# overpoweredRedLight.net
KiCad netlist of a schematic drawn in EAGLE
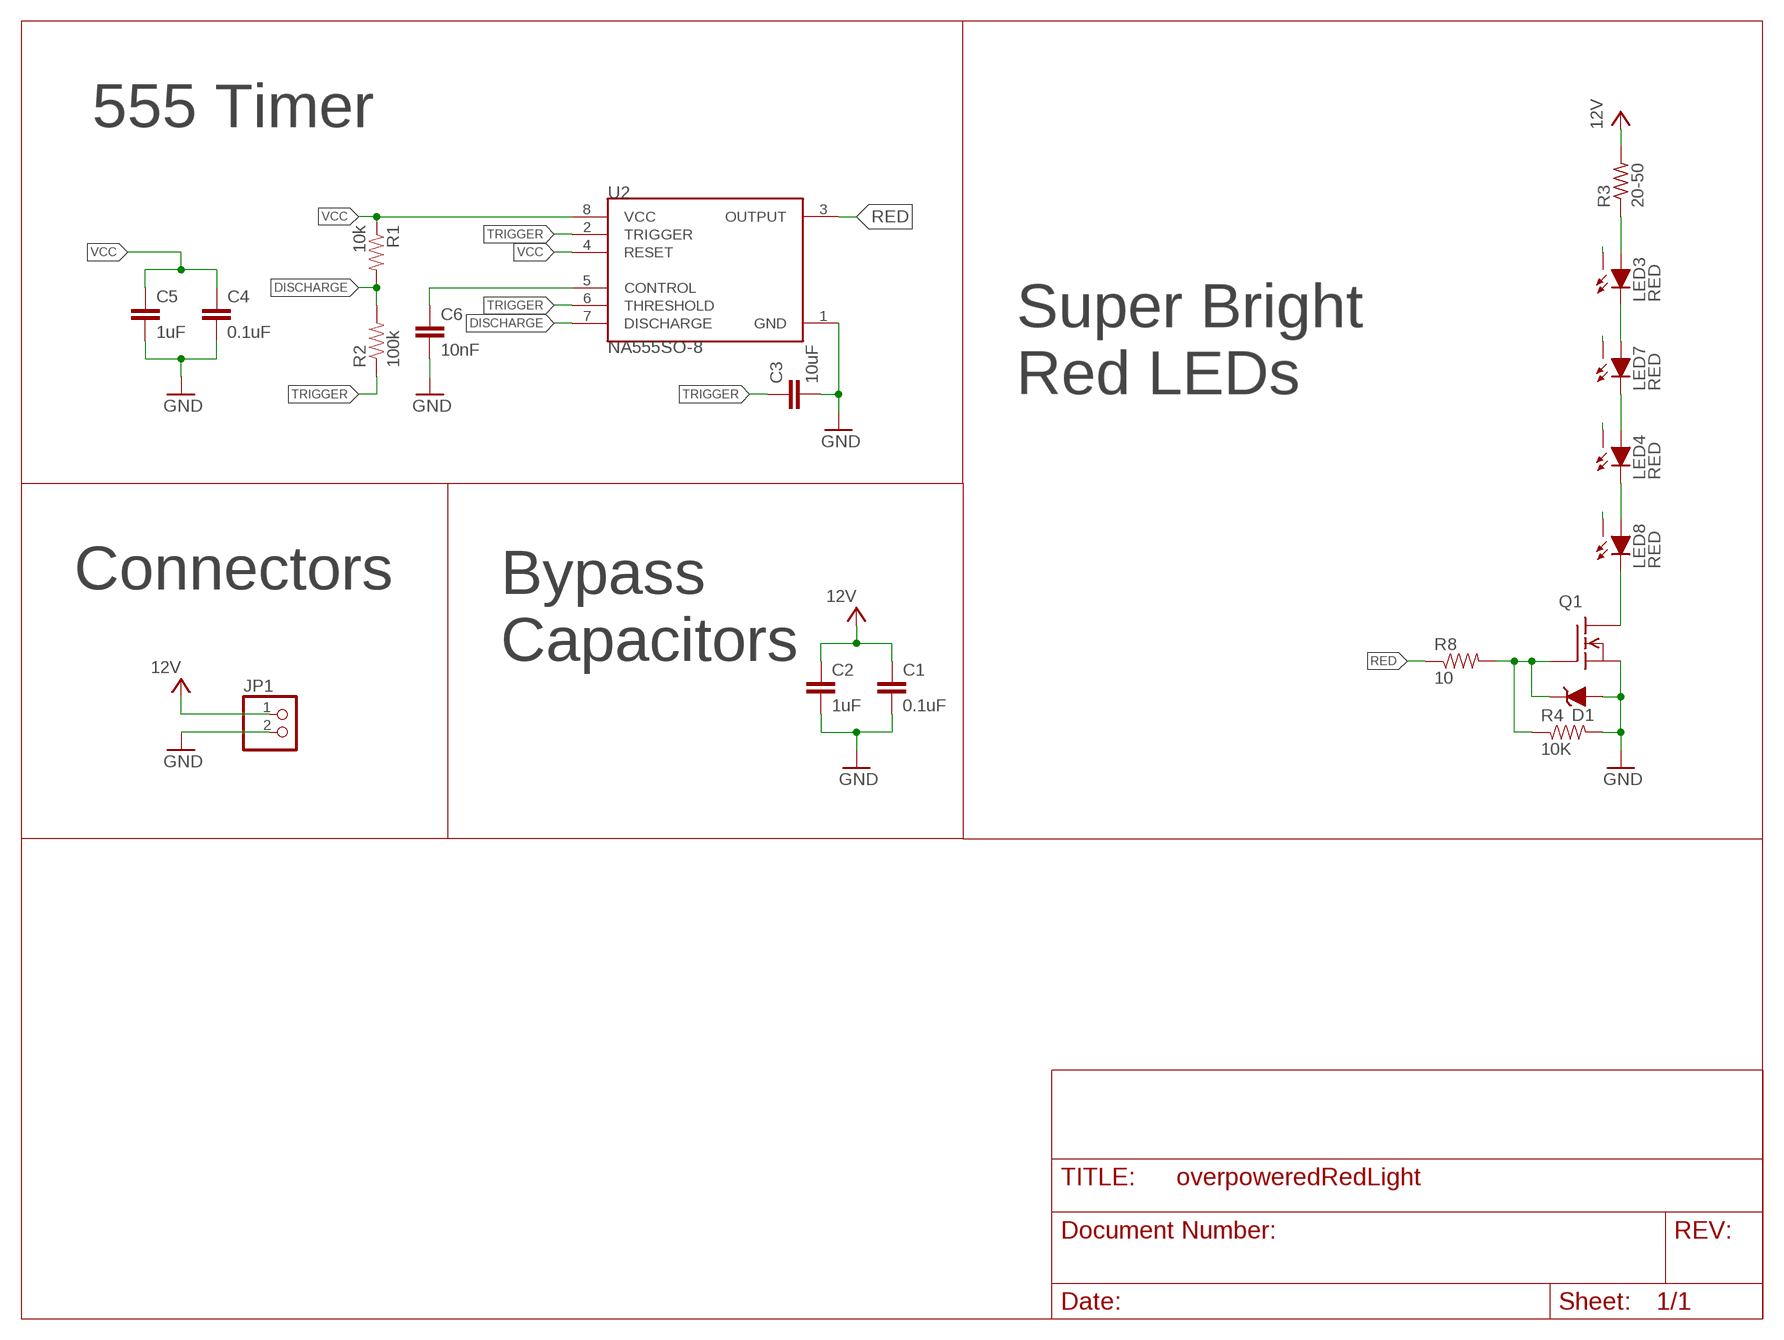
[diagram p0: schematic, sheet 1]

(export (version "E")
  (design (tool "Eeschema 10.0.6"))
  (components
    (comp (ref "C1")
      (value "0.1uF")
      (footprint "eagle-import:0603-CAP")
      (fields (field (name "TOLERANCE") "5%") (field (name "VOLTAGE") "25V"))
      (libsource (lib "eagle-import") (part "CAP0603-CAP"))
    )
    (comp (ref "C2")
      (value "1uF")
      (footprint "eagle-import:0603-CAP")
      (fields (field (name "TOLERANCE") "5%") (field (name "VOLTAGE") "25V"))
      (libsource (lib "eagle-import") (part "CAP0603-CAP"))
    )
    (comp (ref "C3")
      (value "10uF")
      (footprint "eagle-import:0603-CAP")
      (fields (field (name "TOLERANCE") "5%") (field (name "VOLTAGE") "25V"))
      (libsource (lib "eagle-import") (part "CAP0603-CAP"))
    )
    (comp (ref "C4")
      (value "0.1uF")
      (footprint "eagle-import:0603-CAP")
      (fields (field (name "TOLERANCE") "5%") (field (name "VOLTAGE") "25V"))
      (libsource (lib "eagle-import") (part "CAP0603-CAP"))
    )
    (comp (ref "C5")
      (value "1uF")
      (footprint "eagle-import:0603-CAP")
      (fields (field (name "TOLERANCE") "5%") (field (name "VOLTAGE") "25V"))
      (libsource (lib "eagle-import") (part "CAP0603-CAP"))
    )
    (comp (ref "C6")
      (value "10nF")
      (footprint "eagle-import:0603-CAP")
      (fields (field (name "TOLERANCE") "5%") (field (name "VOLTAGE") "25V"))
      (libsource (lib "eagle-import") (part "CAP0603-CAP"))
    )
    (comp (ref "D1")
      (value "MMBZ5246BLT1G")
      (footprint "eagle-import:SOT23")
      (libsource (lib "eagle-import") (part "DIODE_ZENER"))
    )
    (comp (ref "JP1")
      (value "PINHD-1X2")
      (footprint "eagle-import:1X02")
      (libsource (lib "eagle-import") (part "PINHD-1X2"))
    )
    (comp (ref "LED3")
      (value "RED")
      (footprint "eagle-import:XP-E2")
      (libsource (lib "eagle-import") (part "XP-E2XP-E2"))
    )
    (comp (ref "LED4")
      (value "RED")
      (footprint "eagle-import:XP-E2")
      (libsource (lib "eagle-import") (part "XP-E2XP-E2"))
    )
    (comp (ref "LED7")
      (value "RED")
      (footprint "eagle-import:XP-E2")
      (libsource (lib "eagle-import") (part "XP-E2XP-E2"))
    )
    (comp (ref "LED8")
      (value "RED")
      (footprint "eagle-import:XP-E2")
      (libsource (lib "eagle-import") (part "XP-E2XP-E2"))
    )
    (comp (ref "Q1")
      (value "DMG3406LSOT")
      (footprint "eagle-import:SOT23")
      (libsource (lib "eagle-import") (part "DMG3406LSOT"))
    )
    (comp (ref "R1")
      (value "10k")
      (footprint "eagle-import:0603-RES")
      (fields (field (name "TOLERANCE") "1%"))
      (libsource (lib "eagle-import") (part "RESISTOR0603-RES"))
    )
    (comp (ref "R2")
      (value "100k")
      (footprint "eagle-import:0603-RES")
      (fields (field (name "TOLERANCE") "1%"))
      (libsource (lib "eagle-import") (part "RESISTOR0603-RES"))
    )
    (comp (ref "R3")
      (value "20-50")
      (footprint "eagle-import:1W-0.6")
      (libsource (lib "eagle-import") (part "RES_AXIAL1W-0.6"))
    )
    (comp (ref "R4")
      (value "10K")
      (footprint "eagle-import:0603-RES")
      (fields (field (name "TOLERANCE") "1%"))
      (libsource (lib "eagle-import") (part "RESISTOR0603-RES"))
    )
    (comp (ref "R8")
      (value "10")
      (footprint "eagle-import:0603-RES")
      (fields (field (name "TOLERANCE") "1%"))
      (libsource (lib "eagle-import") (part "RESISTOR0603-RES"))
    )
    (comp (ref "U2")
      (value "NA555SO-8")
      (footprint "eagle-import:SOIC-08")
      (libsource (lib "eagle-import") (part "NA555SO-8"))
    )
  )
  (nets
    (net (code "1") (name "/THERM1") (class "Default")
      (node (ref "LED4") (pin "X") (pinfunction "X_X") (pintype "passive"))
      (node (ref "LED8") (pin "X") (pinfunction "X_X") (pintype "passive"))
    )
    (net (code "2") (name "/THERM2") (class "Default")
      (node (ref "LED3") (pin "X") (pinfunction "X_X") (pintype "passive"))
      (node (ref "LED7") (pin "X") (pinfunction "X_X") (pintype "passive"))
    )
    (net (code "3") (name "DISCHARGE") (class "Default")
      (node (ref "R1") (pin "2") (pinfunction "2_2") (pintype "passive"))
      (node (ref "R2") (pin "2") (pinfunction "2_2") (pintype "passive"))
      (node (ref "U2") (pin "7") (pinfunction "DISCHARGE_7") (pintype "passive"))
    )
    (net (code "4") (name "GND") (class "Default")
      (node (ref "C1") (pin "2") (pinfunction "2_2") (pintype "passive"))
      (node (ref "C2") (pin "2") (pinfunction "2_2") (pintype "passive"))
      (node (ref "C3") (pin "2") (pinfunction "2_2") (pintype "passive"))
      (node (ref "C4") (pin "2") (pinfunction "2_2") (pintype "passive"))
      (node (ref "C5") (pin "2") (pinfunction "2_2") (pintype "passive"))
      (node (ref "C6") (pin "2") (pinfunction "2_2") (pintype "passive"))
      (node (ref "D1") (pin "1") (pinfunction "A_1") (pintype "passive"))
      (node (ref "JP1") (pin "2") (pinfunction "2_2") (pintype "passive"))
      (node (ref "Q1") (pin "2") (pinfunction "S_2") (pintype "passive"))
      (node (ref "R4") (pin "2") (pinfunction "2_2") (pintype "passive"))
      (node (ref "U2") (pin "1") (pinfunction "GND_1") (pintype "passive"))
    )
    (net (code "5") (name "Net-(D1-C)") (class "Default")
      (node (ref "D1") (pin "3") (pinfunction "C_3") (pintype "passive"))
      (node (ref "Q1") (pin "1") (pinfunction "G_1") (pintype "passive"))
      (node (ref "R4") (pin "1") (pinfunction "1_1") (pintype "passive"))
      (node (ref "R8") (pin "2") (pinfunction "2_2") (pintype "passive"))
    )
    (net (code "6") (name "Net-(LED3-PadA)") (class "Default")
      (node (ref "LED3") (pin "A") (pinfunction "A_A") (pintype "passive"))
      (node (ref "R3") (pin "1") (pinfunction "1_1") (pintype "passive"))
    )
    (net (code "7") (name "Net-(LED3-PadC)") (class "Default")
      (node (ref "LED3") (pin "C") (pinfunction "C_C") (pintype "passive"))
      (node (ref "LED7") (pin "A") (pinfunction "A_A") (pintype "passive"))
    )
    (net (code "8") (name "Net-(LED4-PadA)") (class "Default")
      (node (ref "LED4") (pin "A") (pinfunction "A_A") (pintype "passive"))
      (node (ref "LED7") (pin "C") (pinfunction "C_C") (pintype "passive"))
    )
    (net (code "9") (name "Net-(LED4-PadC)") (class "Default")
      (node (ref "LED4") (pin "C") (pinfunction "C_C") (pintype "passive"))
      (node (ref "LED8") (pin "A") (pinfunction "A_A") (pintype "passive"))
    )
    (net (code "10") (name "Net-(Q1-D)") (class "Default")
      (node (ref "LED8") (pin "C") (pinfunction "C_C") (pintype "passive"))
      (node (ref "Q1") (pin "3") (pinfunction "D_3") (pintype "passive"))
    )
    (net (code "11") (name "Net-(U2-CONTROL)") (class "Default")
      (node (ref "C6") (pin "1") (pinfunction "1_1") (pintype "passive"))
      (node (ref "U2") (pin "5") (pinfunction "CONTROL_5") (pintype "passive"))
    )
    (net (code "12") (name "RED") (class "Default")
      (node (ref "R8") (pin "1") (pinfunction "1_1") (pintype "passive"))
      (node (ref "U2") (pin "3") (pinfunction "OUTPUT_3") (pintype "passive"))
    )
    (net (code "13") (name "TRIGGER") (class "Default")
      (node (ref "C3") (pin "1") (pinfunction "1_1") (pintype "passive"))
      (node (ref "R2") (pin "1") (pinfunction "1_1") (pintype "passive"))
      (node (ref "U2") (pin "2") (pinfunction "TRIGGER_2") (pintype "passive"))
      (node (ref "U2") (pin "6") (pinfunction "THRESHOLD_6") (pintype "passive"))
    )
    (net (code "14") (name "VCC") (class "Default")
      (node (ref "C1") (pin "1") (pinfunction "1_1") (pintype "passive"))
      (node (ref "C2") (pin "1") (pinfunction "1_1") (pintype "passive"))
      (node (ref "C4") (pin "1") (pinfunction "1_1") (pintype "passive"))
      (node (ref "C5") (pin "1") (pinfunction "1_1") (pintype "passive"))
      (node (ref "JP1") (pin "1") (pinfunction "1_1") (pintype "passive"))
      (node (ref "R1") (pin "1") (pinfunction "1_1") (pintype "passive"))
      (node (ref "R3") (pin "2") (pinfunction "2_2") (pintype "passive"))
      (node (ref "U2") (pin "4") (pinfunction "RESET_4") (pintype "passive"))
      (node (ref "U2") (pin "8") (pinfunction "VCC_8") (pintype "passive"))
    )
  )
)
